# A4988.net
KiCad netlist of a schematic drawn in Altium Designer
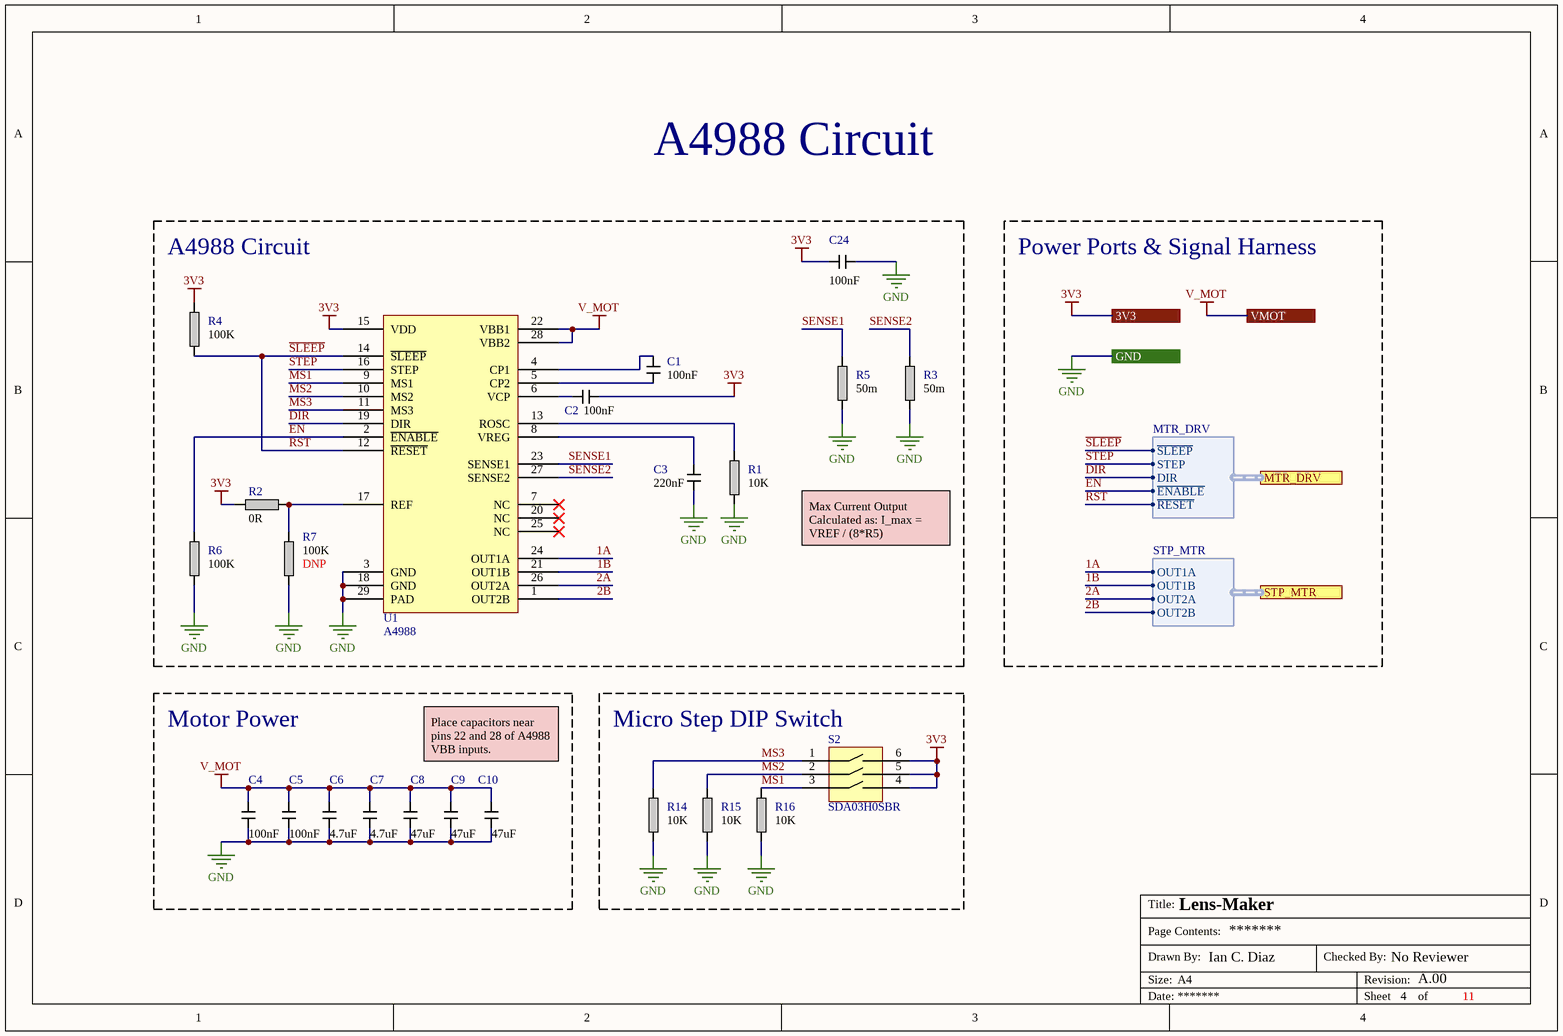
[diagram p0: A4988.SchDoc]

(export (version "E")
  (design (tool "Eeschema 10.0.6"))
  (components
    (comp (ref "C1")
      (value "100nF")
      (footprint "0805")
      (description "50V 100nF X7R ±10% 0805  Multilayer Ceramic Capacitors MLCC - SMD/SMT ROHS")
      (fields
        (field (name "MANUFACTURER") "YAGEO")
        (field (name "MANUFACTURER PART NUMBER") "CC0805KRX7R9BB104")
      )
      (libsource (lib "Library") (part "CAP"))
    )
    (comp (ref "C2")
      (value "100nF")
      (footprint "0805")
      (description "50V 100nF X7R ±10% 0805  Multilayer Ceramic Capacitors MLCC - SMD/SMT ROHS")
      (fields
        (field (name "MANUFACTURER") "YAGEO")
        (field (name "MANUFACTURER PART NUMBER") "CC0805KRX7R9BB104")
      )
      (libsource (lib "Library") (part "CAP"))
    )
    (comp (ref "C3")
      (value "220nF")
      (footprint "0805")
      (description "50V 220nF X7R ±10% 0805  Multilayer Ceramic Capacitors MLCC - SMD/SMT ROHS")
      (fields
        (field (name "MANUFACTURER") "Samsung Electro-Mechanics")
        (field (name "MANUFACTURER PART NUMBER") "CL21B224KBFNNNE")
      )
      (libsource (lib "Library") (part "CAP"))
    )
    (comp (ref "C4")
      (value "100nF")
      (footprint "0805")
      (description "50V 100nF X7R ±10% 0805  Multilayer Ceramic Capacitors MLCC - SMD/SMT ROHS")
      (fields
        (field (name "MANUFACTURER") "YAGEO")
        (field (name "MANUFACTURER PART NUMBER") "CC0805KRX7R9BB104")
      )
      (libsource (lib "Library") (part "CAP"))
    )
    (comp (ref "C5")
      (value "100nF")
      (footprint "0805")
      (description "50V 100nF X7R ±10% 0805  Multilayer Ceramic Capacitors MLCC - SMD/SMT ROHS")
      (fields
        (field (name "MANUFACTURER") "YAGEO")
        (field (name "MANUFACTURER PART NUMBER") "CC0805KRX7R9BB104")
      )
      (libsource (lib "Library") (part "CAP"))
    )
    (comp (ref "C6")
      (value "4.7uF")
      (footprint "0805")
      (description "35V 4.7uF X7R ±10% 0805  Multilayer Ceramic Capacitors MLCC - SMD/SMT ROHS")
      (fields
        (field (name "MANUFACTURER") "Samwha Capacitor")
        (field (name "MANUFACTURER PART NUMBER") "CS2012X7R475K350NRE")
      )
      (libsource (lib "Library") (part "CAP"))
    )
    (comp (ref "C7")
      (value "4.7uF")
      (footprint "0805")
      (description "35V 4.7uF X7R ±10% 0805  Multilayer Ceramic Capacitors MLCC - SMD/SMT ROHS")
      (fields
        (field (name "MANUFACTURER") "Samwha Capacitor")
        (field (name "MANUFACTURER PART NUMBER") "CS2012X7R475K350NRE")
      )
      (libsource (lib "Library") (part "CAP"))
    )
    (comp (ref "C8")
      (value "47uF")
      (footprint "1206")
      (description "25V 47uF X5R ±20% 1206  Multilayer Ceramic Capacitors MLCC - SMD/SMT ROHS")
      (fields
        (field (name "MANUFACTURER") "TDK")
        (field (name "MANUFACTURER PART NUMBER") "C3216X5R1E476MTJ00E")
      )
      (libsource (lib "Library") (part "CAP"))
    )
    (comp (ref "C9")
      (value "47uF")
      (footprint "1206")
      (description "25V 47uF X5R ±20% 1206  Multilayer Ceramic Capacitors MLCC - SMD/SMT ROHS")
      (fields
        (field (name "MANUFACTURER") "TDK")
        (field (name "MANUFACTURER PART NUMBER") "C3216X5R1E476MTJ00E")
      )
      (libsource (lib "Library") (part "CAP"))
    )
    (comp (ref "C10")
      (value "47uF")
      (footprint "1206")
      (description "25V 47uF X5R ±20% 1206  Multilayer Ceramic Capacitors MLCC - SMD/SMT ROHS")
      (fields
        (field (name "MANUFACTURER") "TDK")
        (field (name "MANUFACTURER PART NUMBER") "C3216X5R1E476MTJ00E")
      )
      (libsource (lib "Library") (part "CAP"))
    )
    (comp (ref "C24")
      (value "100nF")
      (footprint "0805")
      (description "50V 100nF X7R ±10% 0805  Multilayer Ceramic Capacitors MLCC - SMD/SMT ROHS")
      (fields
        (field (name "MANUFACTURER") "YAGEO")
        (field (name "MANUFACTURER PART NUMBER") "CC0805KRX7R9BB104")
      )
      (libsource (lib "Library") (part "CAP"))
    )
    (comp (ref "R1")
      (value "10K")
      (footprint "0805")
      (description "125mW Thick Film Resistors ±1% 10kΩ 0805  Chip Resistor - Surface Mount ROHS")
      (fields
        (field (name "MANUFACTURER") "UNI-ROYAL(Uniroyal Elec)")
        (field (name "MANUFACTURER PART NUMBER") "0805W8F1002T5E")
      )
      (libsource (lib "Library") (part "RES"))
    )
    (comp (ref "R2")
      (value "0R")
      (footprint "0805")
      (description "125mW 0Ω 0805 Chip Resistor - Surface Mount ROHS")
      (fields
        (field (name "MANUFACTURER") "PANASONIC")
        (field (name "MANUFACTURER PART NUMBER") "ERJ6GEY0R00V")
      )
      (libsource (lib "") (part "RES_2"))
    )
    (comp (ref "R3")
      (value "50m")
      (footprint "0805")
      (description "250mW ±1% 50mΩ 0805  Chip Resistor - Surface Mount ROHS")
      (fields
        (field (name "MANUFACTURER") "YAGEO")
        (field (name "MANUFACTURER PART NUMBER") "PE0805FRF7W0R05L")
      )
      (libsource (lib "Library") (part "RES"))
    )
    (comp (ref "R4")
      (value "100K")
      (footprint "0805")
      (description "125mW ±5% 100kΩ 0805  Chip Resistor - Surface Mount ROHS")
      (fields
        (field (name "MANUFACTURER") "FH (Guangdong Fenghua Advanced Tech)")
        (field (name "MANUFACTURER PART NUMBER") "RS-05K104JT")
      )
      (libsource (lib "") (part "RES_1"))
    )
    (comp (ref "R5")
      (value "50m")
      (footprint "0805")
      (description "250mW ±1% 50mΩ 0805  Chip Resistor - Surface Mount ROHS")
      (fields
        (field (name "MANUFACTURER") "YAGEO")
        (field (name "MANUFACTURER PART NUMBER") "PE0805FRF7W0R05L")
      )
      (libsource (lib "Library") (part "RES"))
    )
    (comp (ref "R6")
      (value "100K")
      (footprint "0805")
      (description "125mW ±5% 100kΩ 0805  Chip Resistor - Surface Mount ROHS")
      (fields
        (field (name "MANUFACTURER") "FH (Guangdong Fenghua Advanced Tech)")
        (field (name "MANUFACTURER PART NUMBER") "RS-05K104JT")
      )
      (libsource (lib "") (part "RES_1"))
    )
    (comp (ref "R7")
      (value "100K")
      (footprint "0805")
      (description "125mW ±5% 100kΩ 0805  Chip Resistor - Surface Mount ROHS")
      (fields
        (field (name "MANUFACTURER") "FH (Guangdong Fenghua Advanced Tech)")
        (field (name "MANUFACTURER PART NUMBER") "RS-05K104JT")
        (field (name "COMMENTS") "DNP")
      )
      (libsource (lib "") (part "RES_1"))
    )
    (comp (ref "R14")
      (value "10K")
      (footprint "0805")
      (description "125mW Thick Film Resistors ±1% 10kΩ 0805  Chip Resistor - Surface Mount ROHS")
      (fields
        (field (name "MANUFACTURER") "UNI-ROYAL(Uniroyal Elec)")
        (field (name "MANUFACTURER PART NUMBER") "0805W8F1002T5E")
      )
      (libsource (lib "Library") (part "RES"))
    )
    (comp (ref "R15")
      (value "10K")
      (footprint "0805")
      (description "125mW Thick Film Resistors ±1% 10kΩ 0805  Chip Resistor - Surface Mount ROHS")
      (fields
        (field (name "MANUFACTURER") "UNI-ROYAL(Uniroyal Elec)")
        (field (name "MANUFACTURER PART NUMBER") "0805W8F1002T5E")
      )
      (libsource (lib "Library") (part "RES"))
    )
    (comp (ref "R16")
      (value "10K")
      (footprint "0805")
      (description "125mW Thick Film Resistors ±1% 10kΩ 0805  Chip Resistor - Surface Mount ROHS")
      (fields
        (field (name "MANUFACTURER") "UNI-ROYAL(Uniroyal Elec)")
        (field (name "MANUFACTURER PART NUMBER") "0805W8F1002T5E")
      )
      (libsource (lib "Library") (part "RES"))
    )
    (comp (ref "S2")
      (value "DIP SWITCH 3POS")
      (footprint "SDA03H0SBR")
      (description "SWITCH SLIDE DIP SPST 25MA 24V")
      (fields (field (name "MANUFACTURER") "C&K") (field (name "MANUFACTURER PART NUMBER") "SDA03H0SBR"))
      (libsource (lib "Library") (part "DIP SWITCH 3POS"))
    )
    (comp (ref "U1")
      (value "A4988")
      (footprint "28-QFN")
      (description "IC MTR DRVR BIPOLAR 3-5.5V 28QFN")
      (fields
        (field (name "MANUFACTURER") "Allegro MicroSystems, LLC")
        (field (name "MANUFACTURER PART NUMBER") "A4988SETTR-T")
      )
      (libsource (lib "Library") (part "A4988"))
    )
  )
  (nets
    (net (code "3") (name "/1A") (class "Default")
      (node (ref "U1") (pin "24") (pinfunction "OUT1A_24") (pintype "passive"))
    )
    (net (code "4") (name "/1B") (class "Default")
      (node (ref "U1") (pin "21") (pinfunction "OUT1B_21") (pintype "passive"))
    )
    (net (code "5") (name "/2A") (class "Default")
      (node (ref "U1") (pin "26") (pinfunction "OUT2A_26") (pintype "passive"))
    )
    (net (code "6") (name "/2B") (class "Default")
      (node (ref "U1") (pin "1") (pinfunction "OUT2B_1") (pintype "passive"))
    )
    (net (code "7") (name "/DIR") (class "Default")
      (node (ref "U1") (pin "19") (pinfunction "DIR_19") (pintype "passive"))
    )
    (net (code "8") (name "/MS1") (class "Default")
      (node (ref "R16") (pin "2") (pinfunction "2_2") (pintype "passive"))
      (node (ref "S2") (pin "3") (pinfunction "3_3") (pintype "passive"))
      (node (ref "U1") (pin "9") (pinfunction "MS1_9") (pintype "passive"))
    )
    (net (code "9") (name "/MS2") (class "Default")
      (node (ref "R15") (pin "2") (pinfunction "2_2") (pintype "passive"))
      (node (ref "S2") (pin "2") (pinfunction "2_2") (pintype "passive"))
      (node (ref "U1") (pin "10") (pinfunction "MS2_10") (pintype "passive"))
    )
    (net (code "10") (name "/MS3") (class "Default")
      (node (ref "R14") (pin "2") (pinfunction "2_2") (pintype "passive"))
      (node (ref "S2") (pin "1") (pinfunction "1_1") (pintype "passive"))
      (node (ref "U1") (pin "11") (pinfunction "MS3_11") (pintype "passive"))
    )
    (net (code "11") (name "/SENSE1") (class "Default")
      (node (ref "R5") (pin "2") (pinfunction "2_2") (pintype "passive"))
      (node (ref "U1") (pin "23") (pinfunction "SENSE1_23") (pintype "passive"))
    )
    (net (code "12") (name "/SENSE2") (class "Default")
      (node (ref "R3") (pin "2") (pinfunction "2_2") (pintype "passive"))
      (node (ref "U1") (pin "27") (pinfunction "SENSE2_27") (pintype "passive"))
    )
    (net (code "13") (name "/STEP") (class "Default")
      (node (ref "U1") (pin "16") (pinfunction "STEP_16") (pintype "passive"))
    )
    (net (code "16") (name "/~{EN}") (class "Default")
      (node (ref "R6") (pin "1") (pinfunction "1_1") (pintype "passive"))
      (node (ref "U1") (pin "2") (pinfunction "~{ENABLE}_2") (pintype "passive"))
    )
    (net (code "17") (name "/~{RST}") (class "Default")
      (node (ref "R4") (pin "2") (pinfunction "2_2") (pintype "passive"))
      (node (ref "U1") (pin "12") (pinfunction "~{RESET}_12") (pintype "passive"))
      (node (ref "U1") (pin "14") (pinfunction "~{SLEEP}_14") (pintype "passive"))
    )
    (net (code "18") (name "3V3") (class "Default")
      (node (ref "C2") (pin "1") (pintype "passive"))
      (node (ref "C24") (pin "1") (pintype "passive"))
      (node (ref "R2") (pin "2") (pinfunction "2_2") (pintype "passive"))
      (node (ref "R4") (pin "1") (pinfunction "1_1") (pintype "passive"))
      (node (ref "S2") (pin "4") (pinfunction "4_4") (pintype "passive"))
      (node (ref "S2") (pin "5") (pinfunction "5_5") (pintype "passive"))
      (node (ref "S2") (pin "6") (pinfunction "6_6") (pintype "passive"))
      (node (ref "U1") (pin "15") (pinfunction "VDD_15") (pintype "passive"))
    )
    (net (code "19") (name "GND") (class "Default")
      (node (ref "C10") (pin "2") (pintype "passive"))
      (node (ref "C24") (pin "2") (pintype "passive"))
      (node (ref "C3") (pin "1") (pintype "passive"))
      (node (ref "C4") (pin "1") (pintype "passive"))
      (node (ref "C5") (pin "1") (pintype "passive"))
      (node (ref "C6") (pin "2") (pintype "passive"))
      (node (ref "C7") (pin "2") (pintype "passive"))
      (node (ref "C8") (pin "2") (pintype "passive"))
      (node (ref "C9") (pin "2") (pintype "passive"))
      (node (ref "R1") (pin "1") (pinfunction "1_1") (pintype "passive"))
      (node (ref "R14") (pin "1") (pinfunction "1_1") (pintype "passive"))
      (node (ref "R15") (pin "1") (pinfunction "1_1") (pintype "passive"))
      (node (ref "R16") (pin "1") (pinfunction "1_1") (pintype "passive"))
      (node (ref "R3") (pin "1") (pinfunction "1_1") (pintype "passive"))
      (node (ref "R5") (pin "1") (pinfunction "1_1") (pintype "passive"))
      (node (ref "R6") (pin "2") (pinfunction "2_2") (pintype "passive"))
      (node (ref "R7") (pin "2") (pinfunction "2_2") (pintype "passive"))
      (node (ref "U1") (pin "18") (pinfunction "GND_18") (pintype "passive"))
      (node (ref "U1") (pin "29") (pinfunction "PAD_29") (pintype "passive"))
      (node (ref "U1") (pin "3") (pinfunction "GND_3") (pintype "passive"))
    )
    (net (code "20") (name "Net-(U1-CP1)") (class "Default")
      (node (ref "C1") (pin "2") (pintype "passive"))
      (node (ref "U1") (pin "4") (pinfunction "CP1_4") (pintype "passive"))
    )
    (net (code "21") (name "Net-(U1-CP2)") (class "Default")
      (node (ref "C1") (pin "1") (pintype "passive"))
      (node (ref "U1") (pin "5") (pinfunction "CP2_5") (pintype "passive"))
    )
    (net (code "22") (name "Net-(U1-REF)") (class "Default")
      (node (ref "R2") (pin "1") (pinfunction "1_1") (pintype "passive"))
      (node (ref "R7") (pin "1") (pinfunction "1_1") (pintype "passive"))
      (node (ref "U1") (pin "17") (pinfunction "REF_17") (pintype "passive"))
    )
    (net (code "23") (name "Net-(U1-ROSC)") (class "Default")
      (node (ref "R1") (pin "2") (pinfunction "2_2") (pintype "passive"))
      (node (ref "U1") (pin "13") (pinfunction "ROSC_13") (pintype "passive"))
    )
    (net (code "24") (name "Net-(U1-VCP)") (class "Default")
      (node (ref "C2") (pin "2") (pintype "passive"))
      (node (ref "U1") (pin "6") (pinfunction "VCP_6") (pintype "passive"))
    )
    (net (code "25") (name "Net-(U1-VREG)") (class "Default")
      (node (ref "C3") (pin "2") (pintype "passive"))
      (node (ref "U1") (pin "8") (pinfunction "VREG_8") (pintype "passive"))
    )
    (net (code "26") (name "V_MOT") (class "Default")
      (node (ref "C10") (pin "1") (pintype "passive"))
      (node (ref "C4") (pin "2") (pintype "passive"))
      (node (ref "C5") (pin "2") (pintype "passive"))
      (node (ref "C6") (pin "1") (pintype "passive"))
      (node (ref "C7") (pin "1") (pintype "passive"))
      (node (ref "C8") (pin "1") (pintype "passive"))
      (node (ref "C9") (pin "1") (pintype "passive"))
      (node (ref "U1") (pin "22") (pinfunction "VBB1_22") (pintype "passive"))
      (node (ref "U1") (pin "28") (pinfunction "VBB2_28") (pintype "passive"))
    )
    (net (code "27") (name "unconnected-(U1-NC-Pad7)") (class "Default")
      (node (ref "U1") (pin "7") (pinfunction "NC_7") (pintype "passive+no_connect"))
    )
    (net (code "28") (name "unconnected-(U1-NC-Pad20)") (class "Default")
      (node (ref "U1") (pin "20") (pinfunction "NC_20") (pintype "passive+no_connect"))
    )
    (net (code "29") (name "unconnected-(U1-NC-Pad25)") (class "Default")
      (node (ref "U1") (pin "25") (pinfunction "NC_25") (pintype "passive+no_connect"))
    )
  )
)
